# ADC_Decoupling.net
KiCad netlist of a schematic drawn in Altium Designer
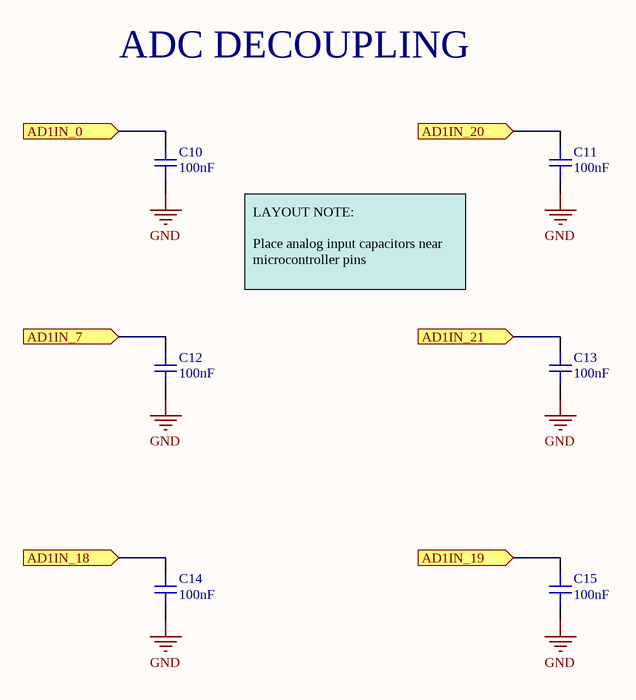
[diagram p0: ADC_Decoupling.SchDoc]

(export (version "E")
  (design (tool "Eeschema 10.0.6"))
  (components
    (comp (ref "C10")
      (value "100nF")
      (footprint "PHANTOM_FOOTPRINTS:C0805")
      (description "CAP MLCC 100nF 10Volts U2J 5%")
      (fields
        (field (name "MANUFACTURER") "Murata")
        (field (name "MANUFACTURER PART NUMBER") "GRM21B7U1A104JA01L")
      )
      (libsource (lib "PHANTOM_LIBRARY") (part "GRM21B7U1A104JA01L"))
    )
    (comp (ref "C11")
      (value "100nF")
      (footprint "PHANTOM_FOOTPRINTS:C0805")
      (description "CAP MLCC 100nF 10Volts U2J 5%")
      (fields
        (field (name "MANUFACTURER") "Murata")
        (field (name "MANUFACTURER PART NUMBER") "GRM21B7U1A104JA01L")
      )
      (libsource (lib "PHANTOM_LIBRARY") (part "GRM21B7U1A104JA01L"))
    )
    (comp (ref "C12")
      (value "100nF")
      (footprint "PHANTOM_FOOTPRINTS:C0805")
      (description "CAP MLCC 100nF 10Volts U2J 5%")
      (fields
        (field (name "MANUFACTURER") "Murata")
        (field (name "MANUFACTURER PART NUMBER") "GRM21B7U1A104JA01L")
      )
      (libsource (lib "PHANTOM_LIBRARY") (part "GRM21B7U1A104JA01L"))
    )
    (comp (ref "C13")
      (value "100nF")
      (footprint "PHANTOM_FOOTPRINTS:C0805")
      (description "CAP MLCC 100nF 10Volts U2J 5%")
      (fields
        (field (name "MANUFACTURER") "Murata")
        (field (name "MANUFACTURER PART NUMBER") "GRM21B7U1A104JA01L")
      )
      (libsource (lib "PHANTOM_LIBRARY") (part "GRM21B7U1A104JA01L"))
    )
    (comp (ref "C14")
      (value "100nF")
      (footprint "PHANTOM_FOOTPRINTS:C0805")
      (description "CAP MLCC 100nF 10Volts U2J 5%")
      (fields
        (field (name "MANUFACTURER") "Murata")
        (field (name "MANUFACTURER PART NUMBER") "GRM21B7U1A104JA01L")
      )
      (libsource (lib "PHANTOM_LIBRARY") (part "GRM21B7U1A104JA01L"))
    )
    (comp (ref "C15")
      (value "100nF")
      (footprint "PHANTOM_FOOTPRINTS:C0805")
      (description "CAP MLCC 100nF 10Volts U2J 5%")
      (fields
        (field (name "MANUFACTURER") "Murata")
        (field (name "MANUFACTURER PART NUMBER") "GRM21B7U1A104JA01L")
      )
      (libsource (lib "PHANTOM_LIBRARY") (part "GRM21B7U1A104JA01L"))
    )
  )
  (nets
    (net (code "1") (name "/AD1IN_0") (class "Default")
      (node (ref "C10") (pin "2") (pinfunction "2_2") (pintype "passive"))
    )
    (net (code "2") (name "/AD1IN_7") (class "Default")
      (node (ref "C12") (pin "2") (pinfunction "2_2") (pintype "passive"))
    )
    (net (code "3") (name "/AD1IN_18") (class "Default")
      (node (ref "C14") (pin "2") (pinfunction "2_2") (pintype "passive"))
    )
    (net (code "4") (name "/AD1IN_19") (class "Default")
      (node (ref "C15") (pin "2") (pinfunction "2_2") (pintype "passive"))
    )
    (net (code "5") (name "/AD1IN_20") (class "Default")
      (node (ref "C11") (pin "2") (pinfunction "2_2") (pintype "passive"))
    )
    (net (code "6") (name "/AD1IN_21") (class "Default")
      (node (ref "C13") (pin "2") (pinfunction "2_2") (pintype "passive"))
    )
    (net (code "7") (name "GND") (class "Default")
      (node (ref "C10") (pin "1") (pinfunction "1_1") (pintype "passive"))
      (node (ref "C11") (pin "1") (pinfunction "1_1") (pintype "passive"))
      (node (ref "C12") (pin "1") (pinfunction "1_1") (pintype "passive"))
      (node (ref "C13") (pin "1") (pinfunction "1_1") (pintype "passive"))
      (node (ref "C14") (pin "1") (pinfunction "1_1") (pintype "passive"))
      (node (ref "C15") (pin "1") (pinfunction "1_1") (pintype "passive"))
    )
  )
)
